# LCD_T20FGS02.net
KiCad netlist of a schematic drawn in Altium Designer
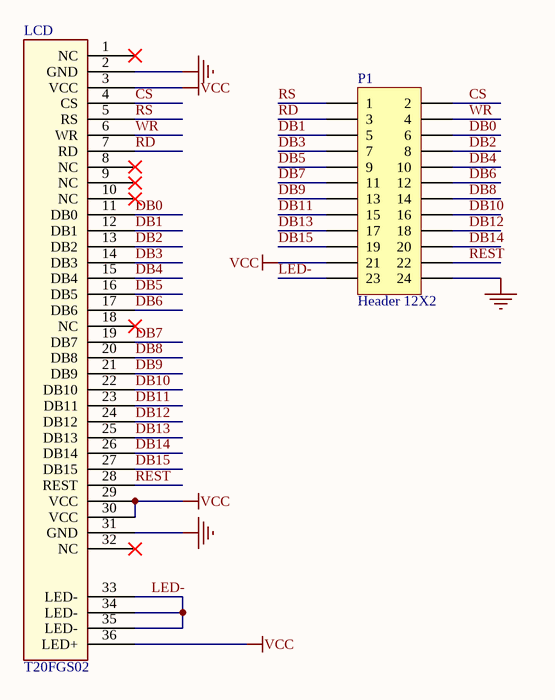
[diagram p0: LCD_T20FGS02.SchDoc]

(export (version "E")
  (design (tool "Eeschema 10.0.6"))
  (components
    (comp (ref "LCD")
      (value "T20FGS02")
      (footprint "LCD_T20FGS02")
      (libsource (lib "Tiky") (part "LCD_T20FGS02"))
    )
    (comp (ref "P1")
      (value "Header 12X2")
      (footprint "HDR2X12")
      (description "Header, 12-Pin, Dual row")
      (fields (field (name "PUBLISHER") "Altium Limited"))
      (libsource (lib "Miscellaneous Connectors") (part "Header 12X2"))
    )
  )
  (nets
    (net (code "1") (name "/CS") (class "Default")
      (node (ref "LCD") (pin "4") (pinfunction "CS_4") (pintype "passive"))
      (node (ref "P1") (pin "2") (pinfunction "2_2") (pintype "passive"))
    )
    (net (code "2") (name "/DB0") (class "Default")
      (node (ref "LCD") (pin "11") (pinfunction "DB0_11") (pintype "passive"))
      (node (ref "P1") (pin "6") (pinfunction "6_6") (pintype "passive"))
    )
    (net (code "3") (name "/DB1") (class "Default")
      (node (ref "LCD") (pin "12") (pinfunction "DB1_12") (pintype "passive"))
      (node (ref "P1") (pin "5") (pinfunction "5_5") (pintype "passive"))
    )
    (net (code "4") (name "/DB2") (class "Default")
      (node (ref "LCD") (pin "13") (pinfunction "DB2_13") (pintype "passive"))
      (node (ref "P1") (pin "8") (pinfunction "8_8") (pintype "passive"))
    )
    (net (code "5") (name "/DB3") (class "Default")
      (node (ref "LCD") (pin "14") (pinfunction "DB3_14") (pintype "passive"))
      (node (ref "P1") (pin "7") (pinfunction "7_7") (pintype "passive"))
    )
    (net (code "6") (name "/DB4") (class "Default")
      (node (ref "LCD") (pin "15") (pinfunction "DB4_15") (pintype "passive"))
      (node (ref "P1") (pin "10") (pinfunction "10_10") (pintype "passive"))
    )
    (net (code "7") (name "/DB5") (class "Default")
      (node (ref "LCD") (pin "16") (pinfunction "DB5_16") (pintype "passive"))
      (node (ref "P1") (pin "9") (pinfunction "9_9") (pintype "passive"))
    )
    (net (code "8") (name "/DB6") (class "Default")
      (node (ref "LCD") (pin "17") (pinfunction "DB6_17") (pintype "passive"))
      (node (ref "P1") (pin "12") (pinfunction "12_12") (pintype "passive"))
    )
    (net (code "9") (name "/DB7") (class "Default")
      (node (ref "LCD") (pin "19") (pinfunction "DB7_19") (pintype "passive"))
      (node (ref "P1") (pin "11") (pinfunction "11_11") (pintype "passive"))
    )
    (net (code "10") (name "/DB8") (class "Default")
      (node (ref "LCD") (pin "20") (pinfunction "DB8_20") (pintype "passive"))
      (node (ref "P1") (pin "14") (pinfunction "14_14") (pintype "passive"))
    )
    (net (code "11") (name "/DB9") (class "Default")
      (node (ref "LCD") (pin "21") (pinfunction "DB9_21") (pintype "passive"))
      (node (ref "P1") (pin "13") (pinfunction "13_13") (pintype "passive"))
    )
    (net (code "12") (name "/DB10") (class "Default")
      (node (ref "LCD") (pin "22") (pinfunction "DB10_22") (pintype "passive"))
      (node (ref "P1") (pin "16") (pinfunction "16_16") (pintype "passive"))
    )
    (net (code "13") (name "/DB11") (class "Default")
      (node (ref "LCD") (pin "23") (pinfunction "DB11_23") (pintype "passive"))
      (node (ref "P1") (pin "15") (pinfunction "15_15") (pintype "passive"))
    )
    (net (code "14") (name "/DB12") (class "Default")
      (node (ref "LCD") (pin "24") (pinfunction "DB12_24") (pintype "passive"))
      (node (ref "P1") (pin "18") (pinfunction "18_18") (pintype "passive"))
    )
    (net (code "15") (name "/DB13") (class "Default")
      (node (ref "LCD") (pin "25") (pinfunction "DB13_25") (pintype "passive"))
      (node (ref "P1") (pin "17") (pinfunction "17_17") (pintype "passive"))
    )
    (net (code "16") (name "/DB14") (class "Default")
      (node (ref "LCD") (pin "26") (pinfunction "DB14_26") (pintype "passive"))
      (node (ref "P1") (pin "20") (pinfunction "20_20") (pintype "passive"))
    )
    (net (code "17") (name "/DB15") (class "Default")
      (node (ref "LCD") (pin "27") (pinfunction "DB15_27") (pintype "passive"))
      (node (ref "P1") (pin "19") (pinfunction "19_19") (pintype "passive"))
    )
    (net (code "18") (name "/LED-") (class "Default")
      (node (ref "LCD") (pin "33") (pinfunction "LED-_33") (pintype "passive"))
      (node (ref "LCD") (pin "34") (pinfunction "LED-_34") (pintype "passive"))
      (node (ref "LCD") (pin "35") (pinfunction "LED-_35") (pintype "passive"))
      (node (ref "P1") (pin "23") (pinfunction "23_23") (pintype "passive"))
    )
    (net (code "19") (name "/RD") (class "Default")
      (node (ref "LCD") (pin "7") (pinfunction "RD_7") (pintype "passive"))
      (node (ref "P1") (pin "3") (pinfunction "3_3") (pintype "passive"))
    )
    (net (code "20") (name "/REST") (class "Default")
      (node (ref "LCD") (pin "28") (pinfunction "REST_28") (pintype "passive"))
      (node (ref "P1") (pin "22") (pinfunction "22_22") (pintype "passive"))
    )
    (net (code "21") (name "/RS") (class "Default")
      (node (ref "LCD") (pin "5") (pinfunction "RS_5") (pintype "passive"))
      (node (ref "P1") (pin "1") (pinfunction "1_1") (pintype "passive"))
    )
    (net (code "22") (name "/WR") (class "Default")
      (node (ref "LCD") (pin "6") (pinfunction "WR_6") (pintype "passive"))
      (node (ref "P1") (pin "4") (pinfunction "4_4") (pintype "passive"))
    )
    (net (code "23") (name "GND") (class "Default")
      (node (ref "LCD") (pin "2") (pinfunction "GND_2") (pintype "passive"))
      (node (ref "LCD") (pin "31") (pinfunction "GND_31") (pintype "passive"))
      (node (ref "P1") (pin "24") (pinfunction "24_24") (pintype "passive"))
    )
    (net (code "24") (name "VCC") (class "Default")
      (node (ref "LCD") (pin "29") (pinfunction "VCC_29") (pintype "passive"))
      (node (ref "LCD") (pin "3") (pinfunction "VCC_3") (pintype "passive"))
      (node (ref "LCD") (pin "30") (pinfunction "VCC_30") (pintype "passive"))
      (node (ref "LCD") (pin "36") (pinfunction "LED+_36") (pintype "passive"))
      (node (ref "P1") (pin "21") (pinfunction "21_21") (pintype "passive"))
    )
    (net (code "25") (name "unconnected-(LCD-NC-Pad1)") (class "Default")
      (node (ref "LCD") (pin "1") (pinfunction "NC_1") (pintype "passive+no_connect"))
    )
    (net (code "26") (name "unconnected-(LCD-NC-Pad8)") (class "Default")
      (node (ref "LCD") (pin "8") (pinfunction "NC_8") (pintype "passive+no_connect"))
    )
    (net (code "27") (name "unconnected-(LCD-NC-Pad9)") (class "Default")
      (node (ref "LCD") (pin "9") (pinfunction "NC_9") (pintype "passive+no_connect"))
    )
    (net (code "28") (name "unconnected-(LCD-NC-Pad10)") (class "Default")
      (node (ref "LCD") (pin "10") (pinfunction "NC_10") (pintype "passive+no_connect"))
    )
    (net (code "29") (name "unconnected-(LCD-NC-Pad18)") (class "Default")
      (node (ref "LCD") (pin "18") (pinfunction "NC_18") (pintype "passive+no_connect"))
    )
    (net (code "30") (name "unconnected-(LCD-NC-Pad32)") (class "Default")
      (node (ref "LCD") (pin "32") (pinfunction "NC_32") (pintype "passive+no_connect"))
    )
  )
)
